# ACCELEROMETER.net
KiCad netlist of a schematic drawn in Altium Designer
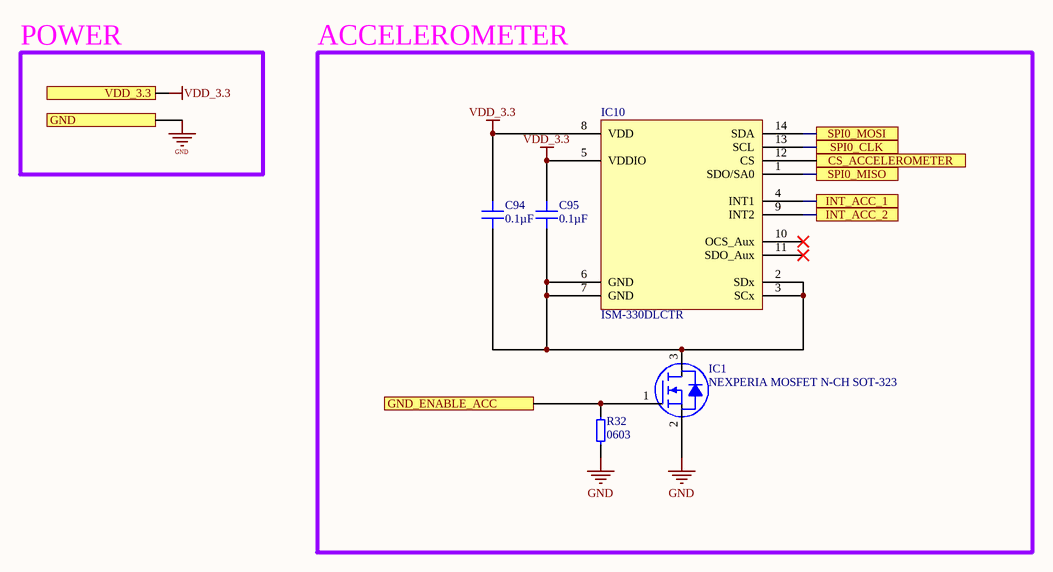
[diagram p0: ACCELEROMETER.SchDoc]

(export (version "E")
  (design (tool "Eeschema 10.0.6"))
  (components
    (comp (ref "C94")
      (value "0.1µF")
      (footprint "CAP 0603_1608 RF")
      (description "CAP CER 0.1UF 16V X7R 0603")
      (fields (field (name "MANUFACTURER") "KEMET") (field (name "VOLTAGE") "16V"))
      (libsource (lib "MVVVMAltiumDatabase") (part "Capacitor"))
    )
    (comp (ref "C95")
      (value "0.1µF")
      (footprint "CAP 0603_1608 RF")
      (description "CAP CER 0.1UF 16V X7R 0603")
      (fields (field (name "MANUFACTURER") "KEMET") (field (name "VOLTAGE") "16V"))
      (libsource (lib "MVVVMAltiumDatabase") (part "Capacitor"))
    )
    (comp (ref "IC1")
      (value "NEXPERIA MOSFET N-CH SOT-323")
      (footprint "NEXPERIA SOT-323")
      (description "MOSFET N-CH 60V 320MA SOT323")
      (fields (field (name "MANUFACTURER") "Nexperia USA Inc."))
      (libsource (lib "MVVVMAltiumDatabase") (part "NEXPERIA MOSFET N-CH SOT-323"))
    )
    (comp (ref "IC10")
      (value "ISM-330DLCTR")
      (footprint "14LGA (2.5MM x 3.0MM)")
      (description "INEMO INERTIAL MODULE")
      (fields (field (name "MANUFACTURER") "STMicroelectronics"))
      (libsource (lib "MVVVMAltiumDatabase") (part "STM ISM330DLCTR"))
    )
    (comp (ref "R32")
      (value "0603")
      (footprint "0603_1608 RF")
      (description "0603 RF Passive")
      (libsource (lib "MVVVMAltiumDatabase") (part "RF Passive"))
    )
  )
  (nets
    (net (code "1") (name "/CS_ACCELEROMETER") (class "Default")
      (node (ref "IC10") (pin "12") (pinfunction "CS_12") (pintype "passive"))
    )
    (net (code "2") (name "/GND_ENABLE_ACC") (class "Default")
      (node (ref "IC1") (pin "1") (pinfunction "G_1") (pintype "passive"))
      (node (ref "R32") (pin "2") (pinfunction "2_2") (pintype "passive"))
    )
    (net (code "3") (name "/INT_ACC_1") (class "Default")
      (node (ref "IC10") (pin "4") (pinfunction "INT1_4") (pintype "passive"))
    )
    (net (code "4") (name "/INT_ACC_2") (class "Default")
      (node (ref "IC10") (pin "9") (pinfunction "INT2_9") (pintype "passive"))
    )
    (net (code "5") (name "/SPI0_CLK") (class "Default")
      (node (ref "IC10") (pin "13") (pinfunction "SCL_13") (pintype "passive"))
    )
    (net (code "6") (name "/SPI0_MISO") (class "Default")
      (node (ref "IC10") (pin "1") (pinfunction "SDO/SA0_1") (pintype "passive"))
    )
    (net (code "7") (name "/SPI0_MOSI") (class "Default")
      (node (ref "IC10") (pin "14") (pinfunction "SDA_14") (pintype "passive"))
    )
    (net (code "8") (name "GND") (class "Default")
      (node (ref "IC1") (pin "2") (pinfunction "S_2") (pintype "passive"))
      (node (ref "R32") (pin "1") (pinfunction "1_1") (pintype "passive"))
    )
    (net (code "9") (name "Net-(IC1-D)") (class "Default")
      (node (ref "C94") (pin "1") (pinfunction "1_1") (pintype "passive"))
      (node (ref "C95") (pin "1") (pinfunction "1_1") (pintype "passive"))
      (node (ref "IC1") (pin "3") (pinfunction "D_3") (pintype "passive"))
      (node (ref "IC10") (pin "2") (pinfunction "SDx_2") (pintype "passive"))
      (node (ref "IC10") (pin "3") (pinfunction "SCx_3") (pintype "passive"))
      (node (ref "IC10") (pin "6") (pinfunction "GND_6") (pintype "power_in"))
      (node (ref "IC10") (pin "7") (pinfunction "GND_7") (pintype "power_in"))
    )
    (net (code "10") (name "VDD_3.3") (class "Default")
      (node (ref "C94") (pin "2") (pinfunction "2_2") (pintype "passive"))
      (node (ref "C95") (pin "2") (pinfunction "2_2") (pintype "passive"))
      (node (ref "IC10") (pin "5") (pinfunction "VDDIO_5") (pintype "power_in"))
      (node (ref "IC10") (pin "8") (pinfunction "VDD_8") (pintype "power_in"))
    )
    (net (code "11") (name "unconnected-(IC10-OCS_Aux-Pad10)") (class "Default")
      (node (ref "IC10") (pin "10") (pinfunction "OCS_Aux_10") (pintype "passive+no_connect"))
    )
    (net (code "12") (name "unconnected-(IC10-SDO_Aux-Pad11)") (class "Default")
      (node (ref "IC10") (pin "11") (pinfunction "SDO_Aux_11") (pintype "passive+no_connect"))
    )
  )
)
